# Driver.net
KiCad netlist of a schematic drawn in Altium Designer
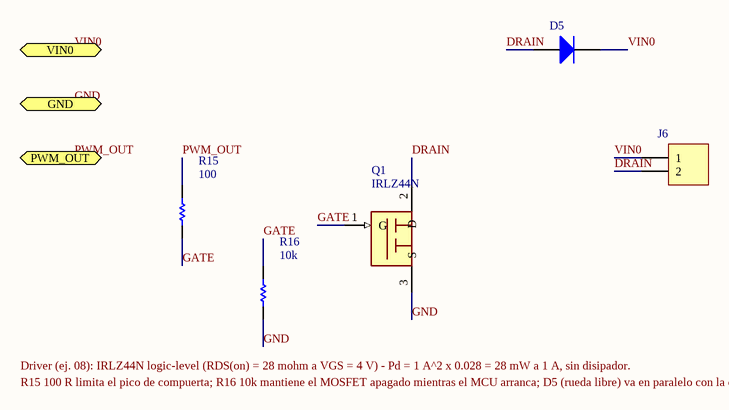
[diagram p0: Driver.SchDoc]

(export (version "E")
  (design (tool "Eeschema 10.0.6"))
  (components
    (comp (ref "D5")
      (value "Diode 1N4007")
      (description "Rueda libre en paralelo con la carga")
      (fields
        (field (name "MANUFACTURER") "Diodes Inc.")
        (field (name "MANUFACTURER PART NUMBER") "1N4007")
        (field (name "PUBLISHER") "Altium Limited")
      )
      (libsource (lib "Miscellaneous Devices") (part "Diode 1N4007"))
    )
    (comp (ref "J6")
      (value "Header 2")
      (description "Carga externa: pin1 VIN, pin2 DRAIN")
      (fields
        (field (name "MANUFACTURER") "Generic")
        (field (name "MANUFACTURER PART NUMBER") "Pin header 1x2 / borne")
        (field (name "PUBLISHER") "Altium Limited")
      )
      (libsource (lib "Miscellaneous Connectors") (part "Header 2"))
    )
    (comp (ref "Q1")
      (value "IRLZ44N")
      (footprint "TO-220AB")
      (description "N-MOSFET logic-level 55 V 47 A TO-220 (G,D,S)")
      (fields (field (name "MANUFACTURER") "Infineon") (field (name "MANUFACTURER PART NUMBER") "IRLZ44NPBF"))
      (libsource (lib "*") (part "IRLZ44N"))
    )
    (comp (ref "R15")
      (value "100")
      (description "Resistor 100 0603")
      (fields
        (field (name "MANUFACTURER") "Yageo")
        (field (name "MANUFACTURER PART NUMBER") "RC0603FR-07100")
        (field (name "PUBLISHER") "Altium Limited")
      )
      (libsource (lib "Miscellaneous Devices") (part "Res1"))
    )
    (comp (ref "R16")
      (value "10k")
      (description "Resistor 10k 0603")
      (fields
        (field (name "MANUFACTURER") "Yageo")
        (field (name "MANUFACTURER PART NUMBER") "RC0603FR-0710K")
        (field (name "PUBLISHER") "Altium Limited")
      )
      (libsource (lib "Miscellaneous Devices") (part "Res1"))
    )
  )
  (nets
    (net (code "1") (name "/DRAIN") (class "Default")
      (node (ref "D5") (pin "1") (pinfunction "A_1") (pintype "passive"))
      (node (ref "J6") (pin "2") (pinfunction "2_2") (pintype "passive"))
      (node (ref "Q1") (pin "2") (pinfunction "D_2") (pintype "passive"))
    )
    (net (code "2") (name "/GATE") (class "Default")
      (node (ref "Q1") (pin "1") (pinfunction "G_1") (pintype "input"))
      (node (ref "R15") (pin "1") (pinfunction "1_1") (pintype "passive"))
      (node (ref "R16") (pin "2") (pinfunction "2_2") (pintype "passive"))
    )
    (net (code "3") (name "/GND") (class "Default")
      (node (ref "Q1") (pin "3") (pinfunction "S_3") (pintype "passive"))
      (node (ref "R16") (pin "1") (pinfunction "1_1") (pintype "passive"))
    )
    (net (code "4") (name "/PWM_OUT") (class "Default")
      (node (ref "R15") (pin "2") (pinfunction "2_2") (pintype "passive"))
    )
    (net (code "5") (name "/VIN0") (class "Default")
      (node (ref "D5") (pin "2") (pinfunction "K_2") (pintype "passive"))
      (node (ref "J6") (pin "1") (pinfunction "1_1") (pintype "passive"))
    )
  )
)
